# giraffe.net
KiCad netlist of a schematic drawn in EAGLE
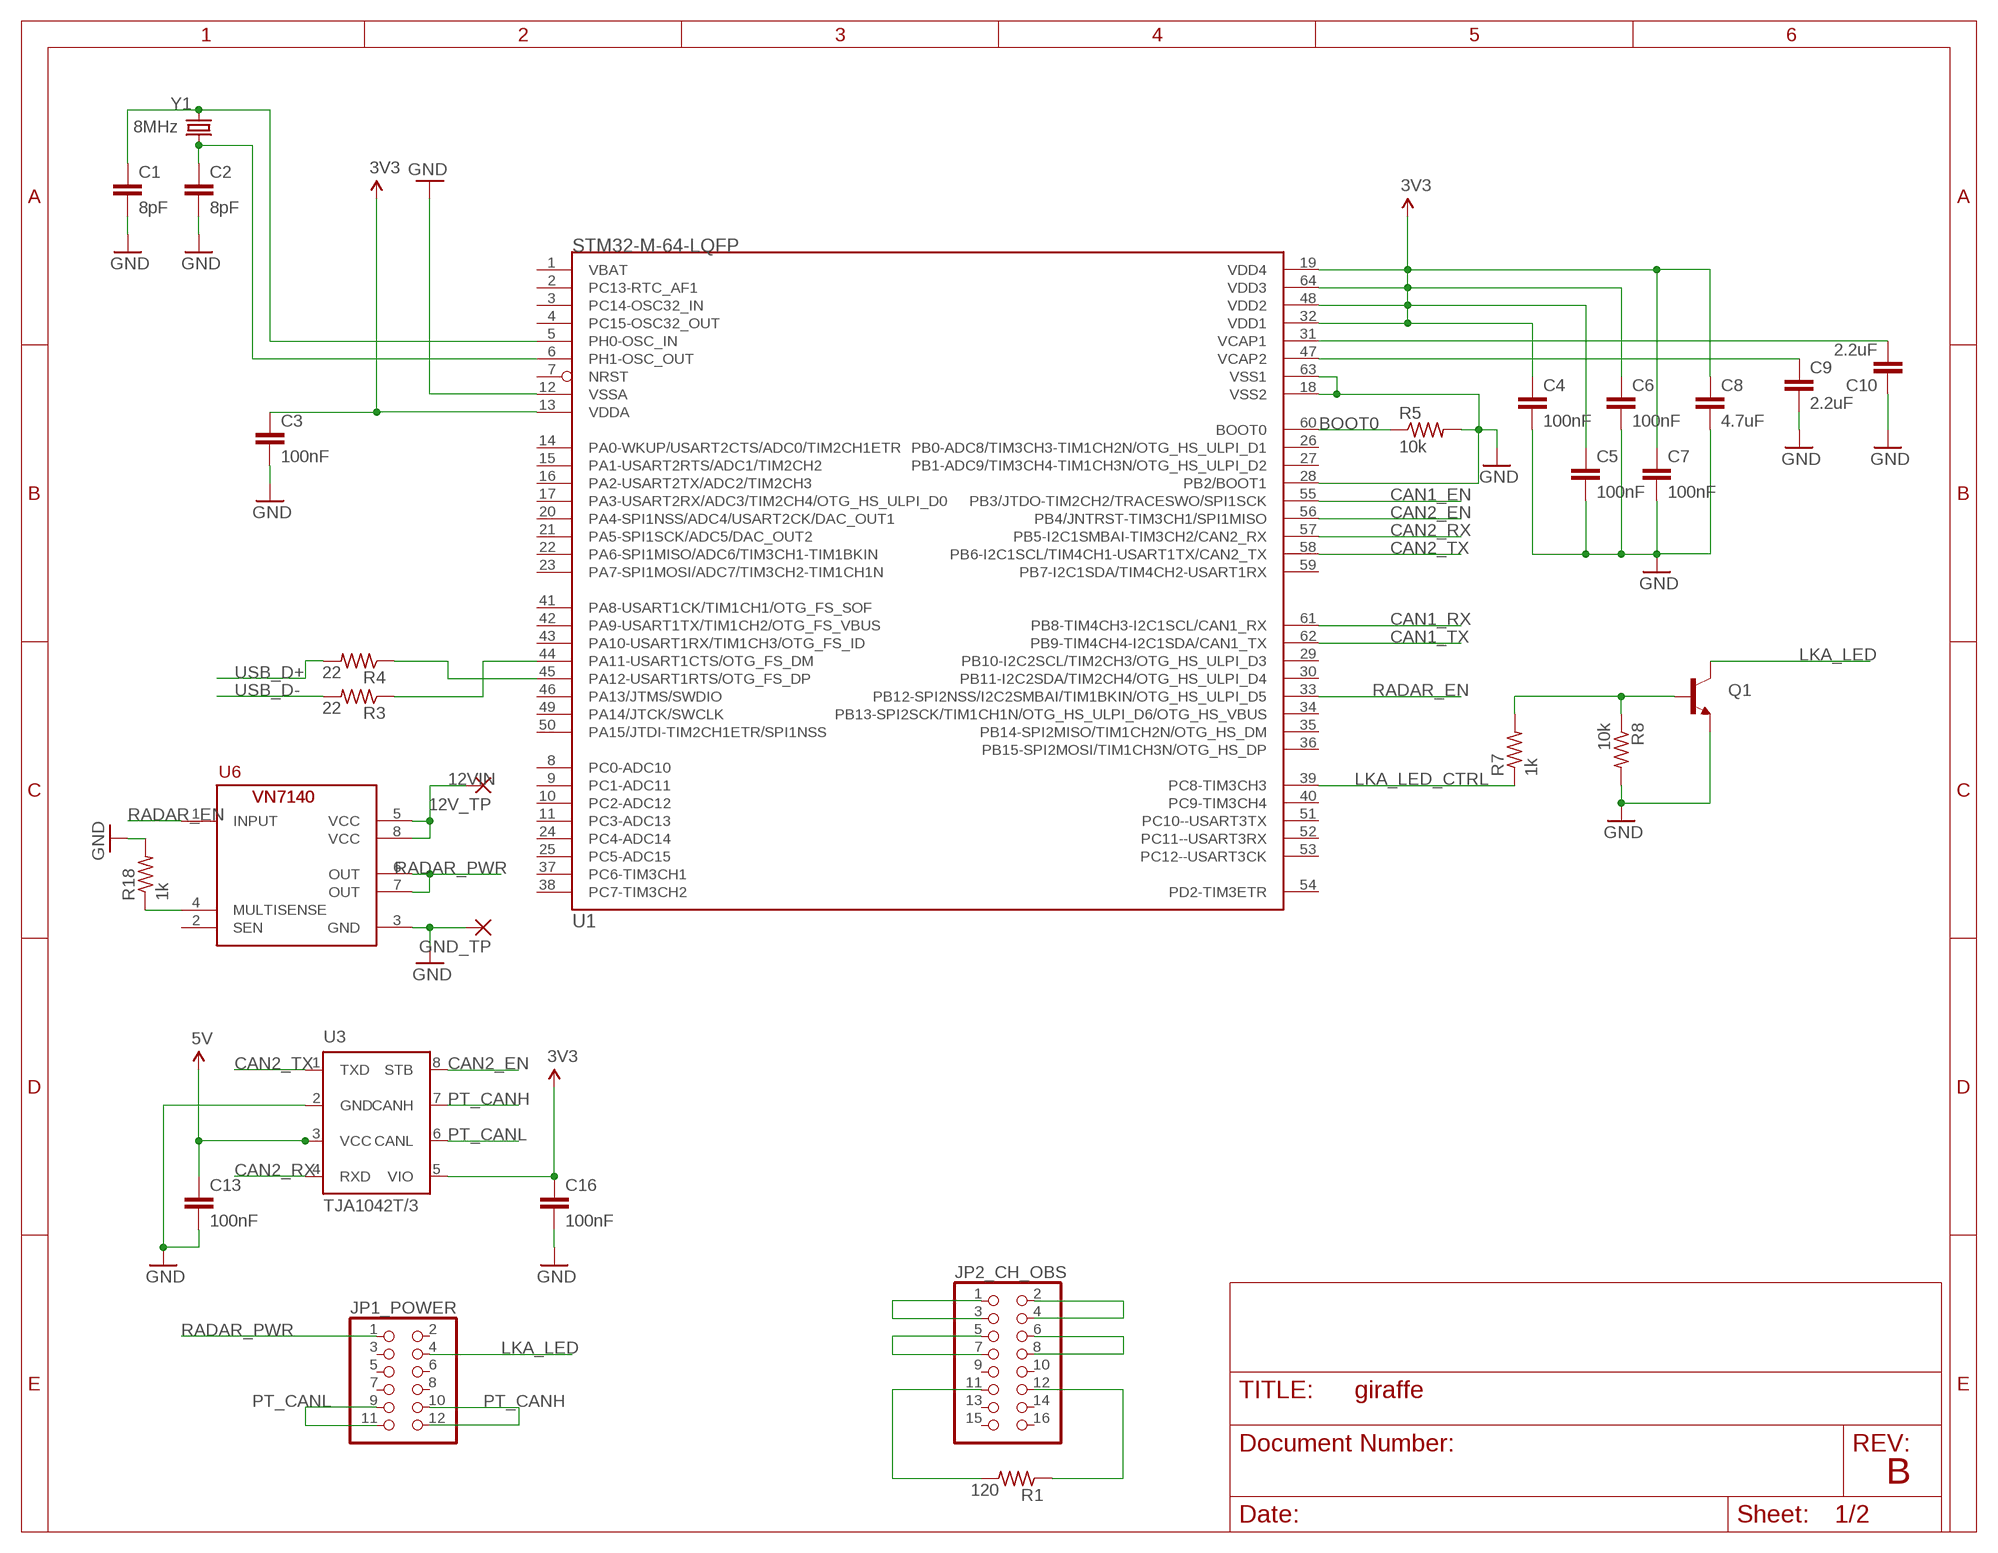
[diagram p0: schematic, sheet 1]
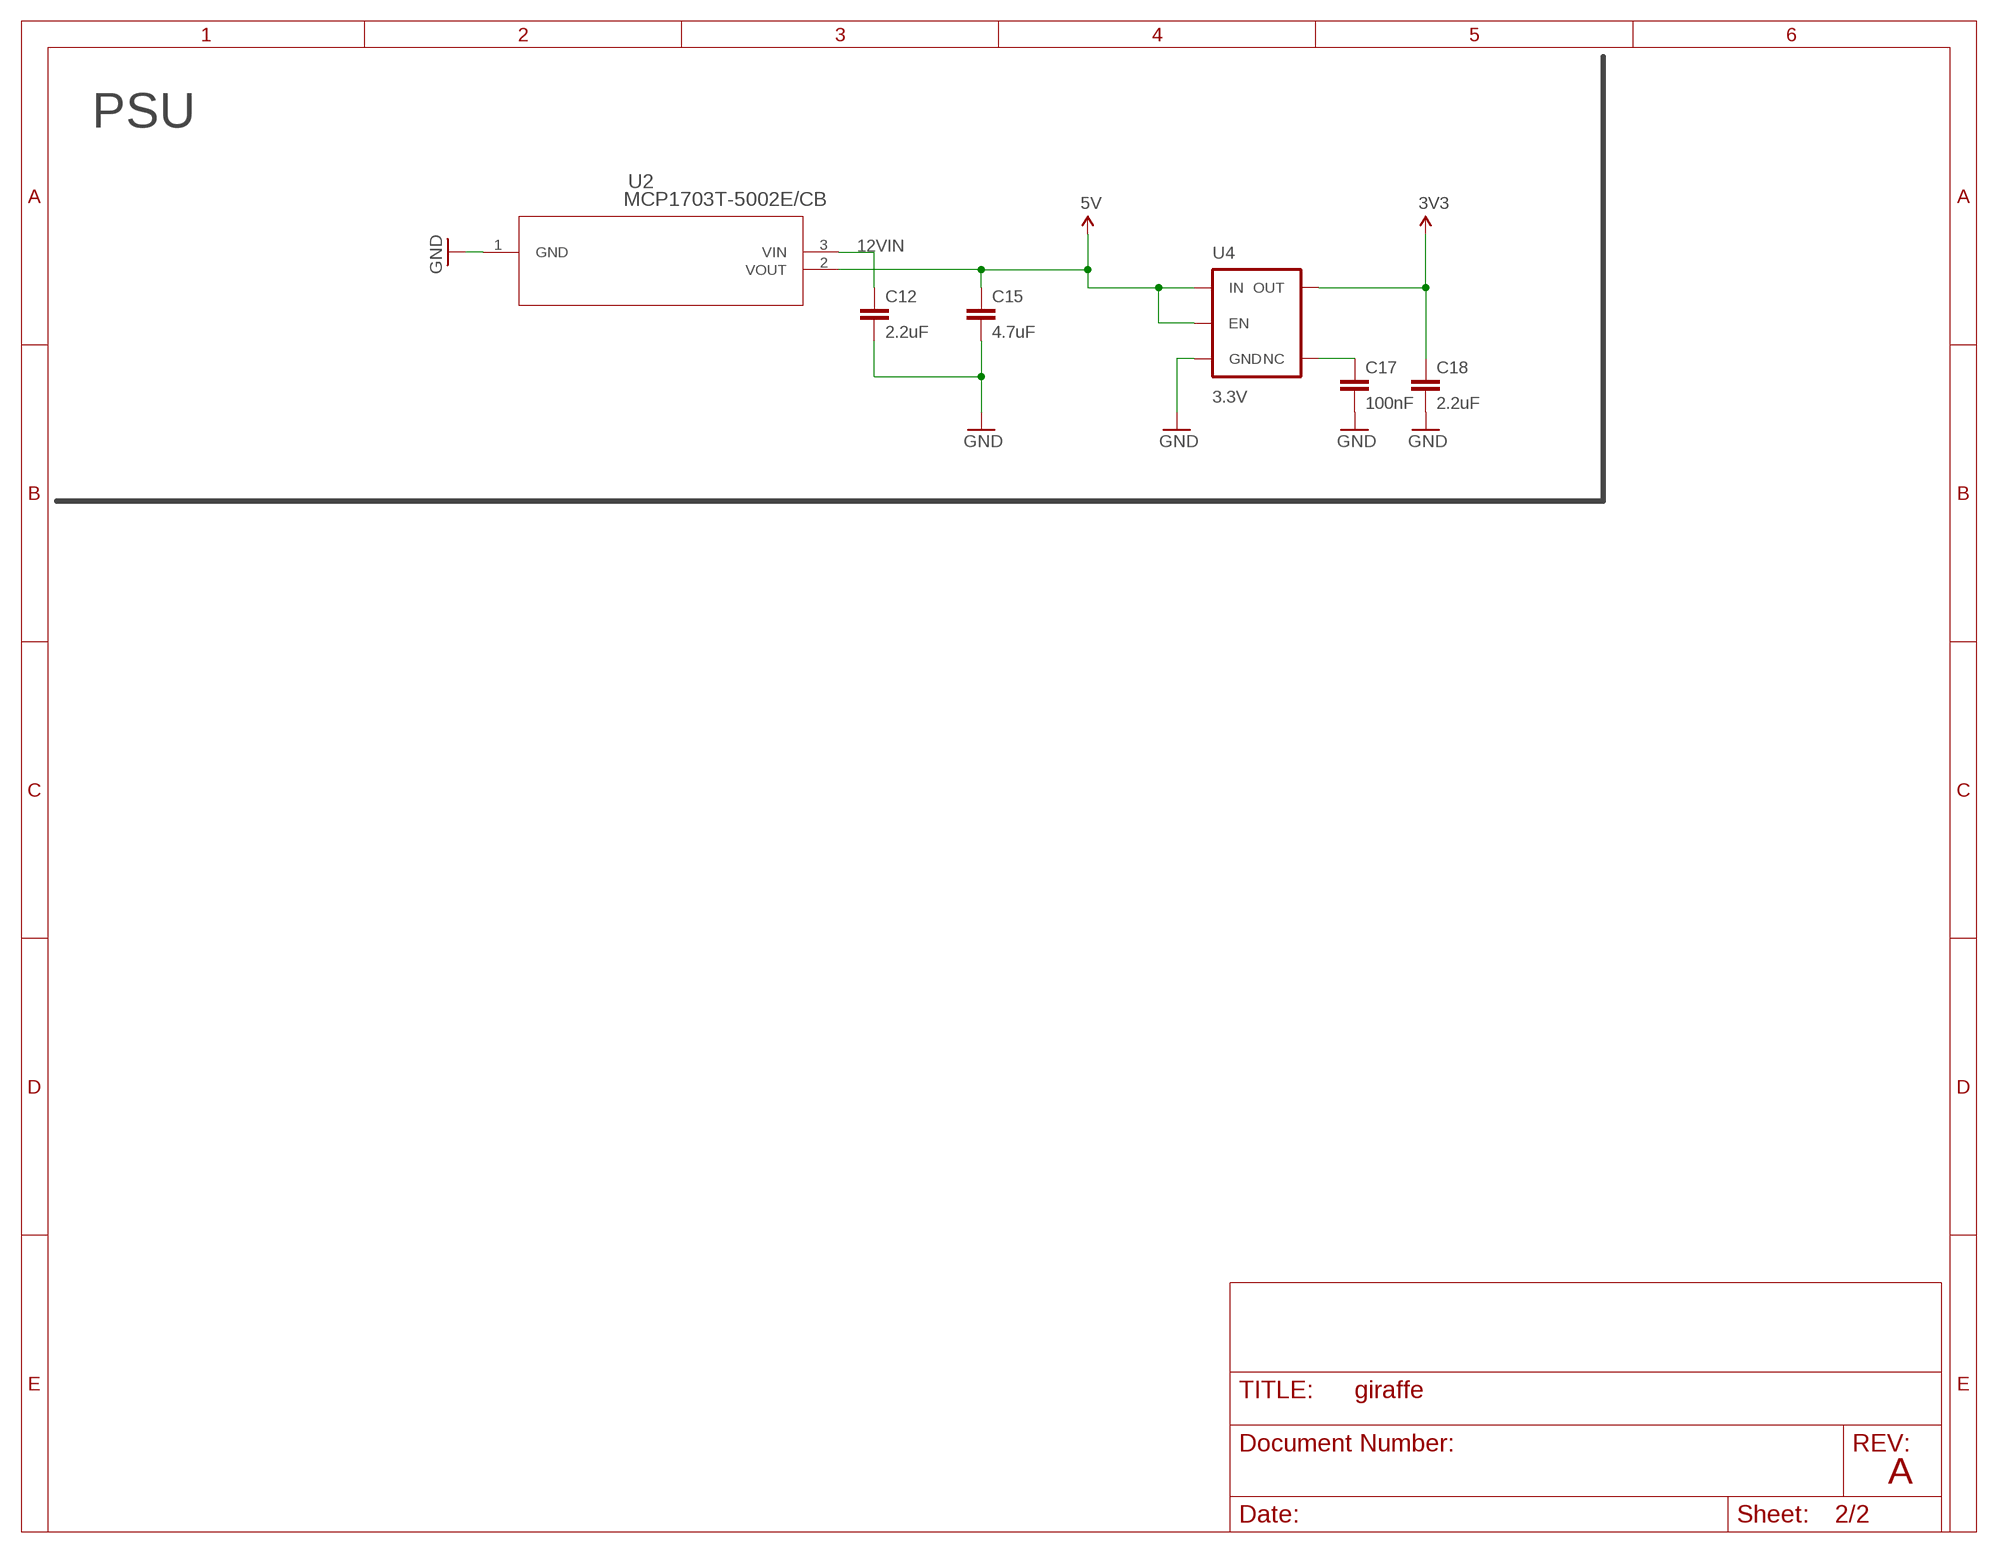
[diagram p1: schematic, sheet 2]

(export (version "E")
  (design (tool "Eeschema 10.0.6"))
  (components
    (comp (ref "C12")
      (value "2.2uF")
      (footprint "eagle-import:0805-CAP")
      (libsource (lib "eagle-import") (part "2.2UF-25V-+80/-20(0805)"))
    )
    (comp (ref "C15")
      (value "4.7uF")
      (footprint "eagle-import:0603-CAP")
      (libsource (lib "eagle-import") (part "CAP0603-CAP"))
    )
    (comp (ref "C17")
      (value "100nF")
      (footprint "eagle-import:0603-CAP")
      (libsource (lib "eagle-import") (part "CAP0603-CAP"))
    )
    (comp (ref "C18")
      (value "2.2uF")
      (footprint "eagle-import:0603-CAP")
      (libsource (lib "eagle-import") (part "CAP0603-CAP"))
    )
    (comp (ref "U2")
      (value "MCP1703T-5002E/CB")
      (footprint "eagle-import:SOT-23A_MC")
      (fields (field (name "MANUFACTURER_PART_NUMBER") "MCP1703T5002ECB"))
      (libsource (lib "eagle-import") (part "MCP1703T-5002E/CB"))
    )
    (comp (ref "U4")
      (value "3.3V")
      (footprint "eagle-import:SOT23-5")
      (libsource (lib "eagle-import") (part "V_REG_AP2112K-3.3V"))
    )
    (comp (ref "12V_TP")
      (value "2,15/1,0")
      (footprint "eagle-import:2,15_1,0")
      (libsource (lib "eagle-import") (part "2,15/1,0"))
    )
    (comp (ref "C1")
      (value "8pF")
      (footprint "eagle-import:0603-CAP")
      (libsource (lib "eagle-import") (part "1.0UF-16V-10%(0603)"))
    )
    (comp (ref "C2")
      (value "8pF")
      (footprint "eagle-import:0603-CAP")
      (libsource (lib "eagle-import") (part "1.0UF-16V-10%(0603)"))
    )
    (comp (ref "C3")
      (value "100nF")
      (footprint "eagle-import:0603-CAP")
      (libsource (lib "eagle-import") (part "1.0UF-16V-10%(0603)"))
    )
    (comp (ref "C4")
      (value "100nF")
      (footprint "eagle-import:0603-CAP")
      (libsource (lib "eagle-import") (part "1.0UF-16V-10%(0603)"))
    )
    (comp (ref "C5")
      (value "100nF")
      (footprint "eagle-import:0603-CAP")
      (libsource (lib "eagle-import") (part "1.0UF-16V-10%(0603)"))
    )
    (comp (ref "C6")
      (value "100nF")
      (footprint "eagle-import:0603-CAP")
      (libsource (lib "eagle-import") (part "0.1UF-25V-5%(0603)"))
    )
    (comp (ref "C7")
      (value "100nF")
      (footprint "eagle-import:0603-CAP")
      (libsource (lib "eagle-import") (part "1.0UF-16V-10%(0603)"))
    )
    (comp (ref "C8")
      (value "4.7uF")
      (footprint "eagle-import:0603-CAP")
      (libsource (lib "eagle-import") (part "1.0UF-16V-10%(0603)"))
    )
    (comp (ref "C9")
      (value "2.2uF")
      (footprint "eagle-import:0603-CAP")
      (libsource (lib "eagle-import") (part "1.0UF-16V-10%(0603)"))
    )
    (comp (ref "C10")
      (value "2.2uF")
      (footprint "eagle-import:0603-CAP")
      (libsource (lib "eagle-import") (part "1.0UF-16V-10%(0603)"))
    )
    (comp (ref "C13")
      (value "100nF")
      (footprint "eagle-import:0603-CAP")
      (libsource (lib "eagle-import") (part "CAP0603-CAP"))
    )
    (comp (ref "C16")
      (value "100nF")
      (footprint "eagle-import:0603-CAP")
      (libsource (lib "eagle-import") (part "CAP0603-CAP"))
    )
    (comp (ref "GND_TP")
      (value "2,15/1,0")
      (footprint "eagle-import:2,15_1,0")
      (libsource (lib "eagle-import") (part "2,15/1,0"))
    )
    (comp (ref "JP1_POWER")
      (value "PINHD-2X6")
      (footprint "eagle-import:2X06")
      (libsource (lib "eagle-import") (part "PINHD-2X6"))
    )
    (comp (ref "JP2_CH_OBS")
      (value "PINHD-2X8")
      (footprint "eagle-import:2X08")
      (libsource (lib "eagle-import") (part "PINHD-2X8"))
    )
    (comp (ref "Q1")
      (value "MMBT2222A")
      (footprint "eagle-import:SOT23-3")
      (libsource (lib "eagle-import") (part "TRANSISTOR_NPNMMBT2222A"))
    )
    (comp (ref "R1")
      (value "120")
      (footprint "eagle-import:R0603")
      (libsource (lib "eagle-import") (part "R-US_R0603"))
    )
    (comp (ref "R3")
      (value "22")
      (footprint "eagle-import:R0603")
      (libsource (lib "eagle-import") (part "R-US_R0603"))
    )
    (comp (ref "R4")
      (value "22")
      (footprint "eagle-import:R0603")
      (libsource (lib "eagle-import") (part "R-US_R0603"))
    )
    (comp (ref "R5")
      (value "10k")
      (footprint "eagle-import:R0603")
      (libsource (lib "eagle-import") (part "R-US_R0603"))
    )
    (comp (ref "R7")
      (value "1k")
      (footprint "eagle-import:R0603")
      (libsource (lib "eagle-import") (part "R-US_R0603"))
    )
    (comp (ref "R8")
      (value "10k")
      (footprint "eagle-import:R0603")
      (libsource (lib "eagle-import") (part "R-US_R0603"))
    )
    (comp (ref "R18")
      (value "1k")
      (footprint "eagle-import:R0603")
      (libsource (lib "eagle-import") (part "R-US_R0603"))
    )
    (comp (ref "U1")
      (value "STM32-M-64-LQFP")
      (footprint "eagle-import:LQFP64")
      (libsource (lib "eagle-import") (part "STM32-M-64-LQFP"))
    )
    (comp (ref "U3")
      (value "TJA1042T/3")
      (footprint "eagle-import:SO-8-L")
      (libsource (lib "eagle-import") (part "TJA1042T/3"))
    )
    (comp (ref "U6")
      (value "VN7140")
      (footprint "eagle-import:SO08")
      (libsource (lib "eagle-import") (part "VN7140"))
    )
    (comp (ref "Y1")
      (value "8MHz")
      (footprint "eagle-import:CRYSTAL-TXC-7A")
      (libsource (lib "eagle-import") (part "CRYSTALTXC-7A"))
    )
  )
  (nets
    (net (code "1") (name "3V3") (class "Default")
      (node (ref "C16") (pin "1") (pinfunction "1_1") (pintype "passive"))
      (node (ref "C18") (pin "1") (pinfunction "1_1") (pintype "passive"))
      (node (ref "C3") (pin "1") (pinfunction "1_1") (pintype "passive"))
      (node (ref "C4") (pin "1") (pinfunction "1_1") (pintype "passive"))
      (node (ref "C5") (pin "1") (pinfunction "1_1") (pintype "passive"))
      (node (ref "C6") (pin "1") (pinfunction "1_1") (pintype "passive"))
      (node (ref "C7") (pin "1") (pinfunction "1_1") (pintype "passive"))
      (node (ref "C8") (pin "1") (pinfunction "1_1") (pintype "passive"))
      (node (ref "U1") (pin "13") (pinfunction "VDDA_13") (pintype "power_in"))
      (node (ref "U1") (pin "19") (pinfunction "VDD4_19") (pintype "bidirectional"))
      (node (ref "U1") (pin "32") (pinfunction "VDD1_32") (pintype "power_in"))
      (node (ref "U1") (pin "48") (pinfunction "VDD2_48") (pintype "power_in"))
      (node (ref "U1") (pin "64") (pinfunction "VDD3_64") (pintype "power_in"))
      (node (ref "U3") (pin "5") (pinfunction "VIO_5") (pintype "power_in"))
      (node (ref "U4") (pin "5") (pinfunction "OUT_5") (pintype "passive"))
    )
    (net (code "2") (name "5V") (class "Default")
      (node (ref "C13") (pin "1") (pinfunction "1_1") (pintype "passive"))
      (node (ref "C15") (pin "1") (pinfunction "1_1") (pintype "passive"))
      (node (ref "U2") (pin "2") (pinfunction "VOUT_2") (pintype "passive"))
      (node (ref "U3") (pin "3") (pinfunction "VCC_3") (pintype "power_in"))
      (node (ref "U4") (pin "1") (pinfunction "IN_1") (pintype "input"))
      (node (ref "U4") (pin "3") (pinfunction "EN_3") (pintype "input"))
    )
    (net (code "3") (name "12VIN") (class "Default")
      (node (ref "12V_TP") (pin "1") (pinfunction "P_1") (pintype "passive"))
      (node (ref "C12") (pin "1") (pinfunction "1_1") (pintype "passive"))
      (node (ref "U2") (pin "3") (pinfunction "VIN_3") (pintype "passive"))
      (node (ref "U6") (pin "5") (pinfunction "VCC_5") (pintype "bidirectional"))
      (node (ref "U6") (pin "8") (pinfunction "VCC_8") (pintype "bidirectional"))
    )
    (net (code "4") (name "BOOT0") (class "Default")
      (node (ref "R5") (pin "1") (pinfunction "1_1") (pintype "passive"))
      (node (ref "U1") (pin "60") (pinfunction "BOOT0_60") (pintype "input"))
    )
    (net (code "5") (name "CAN1_EN") (class "Default")
      (node (ref "U1") (pin "55") (pinfunction "PB3/JTDO-TIM2CH2/TRACESWO/SPI1SCK_55") (pintype "bidirectional"))
    )
    (net (code "6") (name "CAN1_RX") (class "Default")
      (node (ref "U1") (pin "61") (pinfunction "PB8-TIM4CH3-I2C1SCL/CAN1_RX_61") (pintype "bidirectional"))
    )
    (net (code "7") (name "CAN1_TX") (class "Default")
      (node (ref "U1") (pin "62") (pinfunction "PB9-TIM4CH4-I2C1SDA/CAN1_TX_62") (pintype "bidirectional"))
    )
    (net (code "8") (name "CAN2_EN") (class "Default")
      (node (ref "U1") (pin "56") (pinfunction "PB4/JNTRST-TIM3CH1/SPI1MISO_56") (pintype "bidirectional"))
      (node (ref "U3") (pin "8") (pinfunction "STB_8") (pintype "input"))
    )
    (net (code "9") (name "CAN2_RX") (class "Default")
      (node (ref "U1") (pin "57") (pinfunction "PB5-I2C1SMBAI-TIM3CH2/CAN2_RX_57") (pintype "bidirectional"))
      (node (ref "U3") (pin "4") (pinfunction "RXD_4") (pintype "output"))
    )
    (net (code "10") (name "CAN2_TX") (class "Default")
      (node (ref "U1") (pin "58") (pinfunction "PB6-I2C1SCL/TIM4CH1-USART1TX/CAN2_TX_58") (pintype "bidirectional"))
      (node (ref "U3") (pin "1") (pinfunction "TXD_1") (pintype "input"))
    )
    (net (code "11") (name "GND") (class "Default")
      (node (ref "C1") (pin "2") (pinfunction "2_2") (pintype "passive"))
      (node (ref "C10") (pin "1") (pinfunction "1_1") (pintype "passive"))
      (node (ref "C12") (pin "2") (pinfunction "2_2") (pintype "passive"))
      (node (ref "C13") (pin "2") (pinfunction "2_2") (pintype "passive"))
      (node (ref "C15") (pin "2") (pinfunction "2_2") (pintype "passive"))
      (node (ref "C16") (pin "2") (pinfunction "2_2") (pintype "passive"))
      (node (ref "C17") (pin "2") (pinfunction "2_2") (pintype "passive"))
      (node (ref "C18") (pin "2") (pinfunction "2_2") (pintype "passive"))
      (node (ref "C2") (pin "2") (pinfunction "2_2") (pintype "passive"))
      (node (ref "C3") (pin "2") (pinfunction "2_2") (pintype "passive"))
      (node (ref "C4") (pin "2") (pinfunction "2_2") (pintype "passive"))
      (node (ref "C5") (pin "2") (pinfunction "2_2") (pintype "passive"))
      (node (ref "C6") (pin "2") (pinfunction "2_2") (pintype "passive"))
      (node (ref "C7") (pin "2") (pinfunction "2_2") (pintype "passive"))
      (node (ref "C8") (pin "2") (pinfunction "2_2") (pintype "passive"))
      (node (ref "C9") (pin "2") (pinfunction "2_2") (pintype "passive"))
      (node (ref "GND_TP") (pin "1") (pinfunction "P_1") (pintype "passive"))
      (node (ref "Q1") (pin "2") (pinfunction "E_2") (pintype "passive"))
      (node (ref "R18") (pin "2") (pinfunction "2_2") (pintype "passive"))
      (node (ref "R5") (pin "2") (pinfunction "2_2") (pintype "passive"))
      (node (ref "R8") (pin "2") (pinfunction "2_2") (pintype "passive"))
      (node (ref "U1") (pin "12") (pinfunction "VSSA_12") (pintype "power_in"))
      (node (ref "U1") (pin "18") (pinfunction "VSS2_18") (pintype "bidirectional"))
      (node (ref "U1") (pin "28") (pinfunction "PB2/BOOT1_28") (pintype "bidirectional"))
      (node (ref "U1") (pin "63") (pinfunction "VSS1_63") (pintype "power_in"))
      (node (ref "U2") (pin "1") (pinfunction "GND_1") (pintype "passive"))
      (node (ref "U3") (pin "2") (pinfunction "GND_2") (pintype "passive"))
      (node (ref "U4") (pin "2") (pinfunction "GND_2") (pintype "input"))
      (node (ref "U6") (pin "3") (pinfunction "GND_3") (pintype "bidirectional"))
    )
    (net (code "12") (name "LKA_LED") (class "Default")
      (node (ref "JP1_POWER") (pin "4") (pinfunction "4_4") (pintype "passive"))
      (node (ref "Q1") (pin "3") (pinfunction "C_3") (pintype "passive"))
    )
    (net (code "13") (name "LKA_LED_CTRL") (class "Default")
      (node (ref "R7") (pin "1") (pinfunction "1_1") (pintype "passive"))
      (node (ref "U1") (pin "39") (pinfunction "PC8-TIM3CH3_39") (pintype "bidirectional"))
    )
    (net (code "14") (name "Net-(JP2_CH_OBS-Pad1)") (class "Default")
      (node (ref "JP2_CH_OBS") (pin "1") (pinfunction "1_1") (pintype "passive"))
      (node (ref "JP2_CH_OBS") (pin "3") (pinfunction "3_3") (pintype "passive"))
    )
    (net (code "15") (name "Net-(JP2_CH_OBS-Pad2)") (class "Default")
      (node (ref "JP2_CH_OBS") (pin "2") (pinfunction "2_2") (pintype "passive"))
      (node (ref "JP2_CH_OBS") (pin "4") (pinfunction "4_4") (pintype "passive"))
    )
    (net (code "16") (name "Net-(JP2_CH_OBS-Pad5)") (class "Default")
      (node (ref "JP2_CH_OBS") (pin "5") (pinfunction "5_5") (pintype "passive"))
      (node (ref "JP2_CH_OBS") (pin "7") (pinfunction "7_7") (pintype "passive"))
    )
    (net (code "17") (name "Net-(JP2_CH_OBS-Pad6)") (class "Default")
      (node (ref "JP2_CH_OBS") (pin "6") (pinfunction "6_6") (pintype "passive"))
      (node (ref "JP2_CH_OBS") (pin "8") (pinfunction "8_8") (pintype "passive"))
    )
    (net (code "18") (name "Net-(JP2_CH_OBS-Pad11)") (class "Default")
      (node (ref "JP2_CH_OBS") (pin "11") (pinfunction "11_11") (pintype "passive"))
      (node (ref "R1") (pin "2") (pinfunction "2_2") (pintype "passive"))
    )
    (net (code "19") (name "Net-(JP2_CH_OBS-Pad12)") (class "Default")
      (node (ref "JP2_CH_OBS") (pin "12") (pinfunction "12_12") (pintype "passive"))
      (node (ref "R1") (pin "1") (pinfunction "1_1") (pintype "passive"))
    )
    (net (code "20") (name "Net-(Q1-B)") (class "Default")
      (node (ref "Q1") (pin "1") (pinfunction "B_1") (pintype "passive"))
      (node (ref "R7") (pin "2") (pinfunction "2_2") (pintype "passive"))
      (node (ref "R8") (pin "1") (pinfunction "1_1") (pintype "passive"))
    )
    (net (code "21") (name "Net-(U1-PA11-USART1CTS{slash}OTG_FS_DM)") (class "Default")
      (node (ref "R3") (pin "1") (pinfunction "1_1") (pintype "passive"))
      (node (ref "U1") (pin "44") (pinfunction "PA11-USART1CTS/OTG_FS_DM_44") (pintype "bidirectional"))
    )
    (net (code "22") (name "Net-(U1-PA12-USART1RTS{slash}OTG_FS_DP)") (class "Default")
      (node (ref "R4") (pin "1") (pinfunction "1_1") (pintype "passive"))
      (node (ref "U1") (pin "45") (pinfunction "PA12-USART1RTS/OTG_FS_DP_45") (pintype "bidirectional"))
    )
    (net (code "23") (name "Net-(U1-PH0-OSC_IN)") (class "Default")
      (node (ref "C1") (pin "1") (pinfunction "1_1") (pintype "passive"))
      (node (ref "U1") (pin "5") (pinfunction "PH0-OSC_IN_5") (pintype "input"))
      (node (ref "Y1") (pin "P$1") (pinfunction "1_P$1") (pintype "passive"))
    )
    (net (code "24") (name "Net-(U1-PH1-OSC_OUT)") (class "Default")
      (node (ref "C2") (pin "1") (pinfunction "1_1") (pintype "passive"))
      (node (ref "U1") (pin "6") (pinfunction "PH1-OSC_OUT_6") (pintype "output"))
      (node (ref "Y1") (pin "P$2") (pinfunction "2_P$2") (pintype "passive"))
    )
    (net (code "25") (name "Net-(U1-VCAP1)") (class "Default")
      (node (ref "C10") (pin "2") (pinfunction "2_2") (pintype "passive"))
      (node (ref "U1") (pin "31") (pinfunction "VCAP1_31") (pintype "power_in"))
    )
    (net (code "26") (name "Net-(U1-VCAP2)") (class "Default")
      (node (ref "C9") (pin "1") (pinfunction "1_1") (pintype "passive"))
      (node (ref "U1") (pin "47") (pinfunction "VCAP2_47") (pintype "power_in"))
    )
    (net (code "27") (name "Net-(U4-NC)") (class "Default")
      (node (ref "C17") (pin "1") (pinfunction "1_1") (pintype "passive"))
      (node (ref "U4") (pin "4") (pinfunction "NC_4") (pintype "input"))
    )
    (net (code "28") (name "Net-(U6-MULTISENSE)") (class "Default")
      (node (ref "R18") (pin "1") (pinfunction "1_1") (pintype "passive"))
      (node (ref "U6") (pin "4") (pinfunction "MULTISENSE_4") (pintype "bidirectional"))
    )
    (net (code "29") (name "PT_CANH") (class "Default")
      (node (ref "JP1_POWER") (pin "10") (pinfunction "10_10") (pintype "passive"))
      (node (ref "JP1_POWER") (pin "12") (pinfunction "12_12") (pintype "passive"))
      (node (ref "U3") (pin "7") (pinfunction "CANH_7") (pintype "output"))
    )
    (net (code "30") (name "PT_CANL") (class "Default")
      (node (ref "JP1_POWER") (pin "11") (pinfunction "11_11") (pintype "passive"))
      (node (ref "JP1_POWER") (pin "9") (pinfunction "9_9") (pintype "passive"))
      (node (ref "U3") (pin "6") (pinfunction "CANL_6") (pintype "output"))
    )
    (net (code "31") (name "RADAR_EN") (class "Default")
      (node (ref "U1") (pin "33") (pinfunction "PB12-SPI2NSS/I2C2SMBAI/TIM1BKIN/OTG_HS_ULPI_D5_33") (pintype "bidirectional"))
      (node (ref "U6") (pin "1") (pinfunction "INPUT_1") (pintype "bidirectional"))
    )
    (net (code "32") (name "RADAR_PWR") (class "Default")
      (node (ref "JP1_POWER") (pin "1") (pinfunction "1_1") (pintype "passive"))
      (node (ref "U6") (pin "6") (pinfunction "OUT_6") (pintype "bidirectional"))
      (node (ref "U6") (pin "7") (pinfunction "OUT_7") (pintype "bidirectional"))
    )
    (net (code "33") (name "USB_D+") (class "Default")
      (node (ref "R4") (pin "2") (pinfunction "2_2") (pintype "passive"))
    )
    (net (code "34") (name "USB_D-") (class "Default")
      (node (ref "R3") (pin "2") (pinfunction "2_2") (pintype "passive"))
    )
    (net (code "35") (name "VBAT") (class "Default")
      (node (ref "U1") (pin "1") (pinfunction "VBAT_1") (pintype "power_in"))
    )
    (net (code "36") (name "unconnected-(JP1_POWER-Pad2)") (class "Default")
      (node (ref "JP1_POWER") (pin "2") (pinfunction "2_2") (pintype "passive"))
    )
    (net (code "37") (name "unconnected-(JP1_POWER-Pad3)") (class "Default")
      (node (ref "JP1_POWER") (pin "3") (pinfunction "3_3") (pintype "passive"))
    )
    (net (code "38") (name "unconnected-(JP1_POWER-Pad5)") (class "Default")
      (node (ref "JP1_POWER") (pin "5") (pinfunction "5_5") (pintype "passive"))
    )
    (net (code "39") (name "unconnected-(JP1_POWER-Pad6)") (class "Default")
      (node (ref "JP1_POWER") (pin "6") (pinfunction "6_6") (pintype "passive"))
    )
    (net (code "40") (name "unconnected-(JP1_POWER-Pad7)") (class "Default")
      (node (ref "JP1_POWER") (pin "7") (pinfunction "7_7") (pintype "passive"))
    )
    (net (code "41") (name "unconnected-(JP1_POWER-Pad8)") (class "Default")
      (node (ref "JP1_POWER") (pin "8") (pinfunction "8_8") (pintype "passive"))
    )
    (net (code "42") (name "unconnected-(JP2_CH_OBS-Pad9)") (class "Default")
      (node (ref "JP2_CH_OBS") (pin "9") (pinfunction "9_9") (pintype "passive"))
    )
    (net (code "43") (name "unconnected-(JP2_CH_OBS-Pad10)") (class "Default")
      (node (ref "JP2_CH_OBS") (pin "10") (pinfunction "10_10") (pintype "passive"))
    )
    (net (code "44") (name "unconnected-(JP2_CH_OBS-Pad13)") (class "Default")
      (node (ref "JP2_CH_OBS") (pin "13") (pinfunction "13_13") (pintype "passive"))
    )
    (net (code "45") (name "unconnected-(JP2_CH_OBS-Pad14)") (class "Default")
      (node (ref "JP2_CH_OBS") (pin "14") (pinfunction "14_14") (pintype "passive"))
    )
    (net (code "46") (name "unconnected-(JP2_CH_OBS-Pad15)") (class "Default")
      (node (ref "JP2_CH_OBS") (pin "15") (pinfunction "15_15") (pintype "passive"))
    )
    (net (code "47") (name "unconnected-(JP2_CH_OBS-Pad16)") (class "Default")
      (node (ref "JP2_CH_OBS") (pin "16") (pinfunction "16_16") (pintype "passive"))
    )
    (net (code "48") (name "unconnected-(U1-NRST-Pad7)") (class "Default")
      (node (ref "U1") (pin "7") (pinfunction "NRST_7") (pintype "bidirectional"))
    )
    (net (code "49") (name "unconnected-(U1-PA0-WKUP{slash}USART2CTS{slash}ADC0{slash}TIM2CH1ETR-Pad14)") (class "Default")
      (node (ref "U1") (pin "14") (pinfunction "PA0-WKUP/USART2CTS/ADC0/TIM2CH1ETR_14") (pintype "bidirectional"))
    )
    (net (code "50") (name "unconnected-(U1-PA1-USART2RTS{slash}ADC1{slash}TIM2CH2-Pad15)") (class "Default")
      (node (ref "U1") (pin "15") (pinfunction "PA1-USART2RTS/ADC1/TIM2CH2_15") (pintype "bidirectional"))
    )
    (net (code "51") (name "unconnected-(U1-PA2-USART2TX{slash}ADC2{slash}TIM2CH3-Pad16)") (class "Default")
      (node (ref "U1") (pin "16") (pinfunction "PA2-USART2TX/ADC2/TIM2CH3_16") (pintype "bidirectional"))
    )
    (net (code "52") (name "unconnected-(U1-PA3-USART2RX{slash}ADC3{slash}TIM2CH4{slash}OTG_HS_ULPI_D0-Pad17)") (class "Default")
      (node (ref "U1") (pin "17") (pinfunction "PA3-USART2RX/ADC3/TIM2CH4/OTG_HS_ULPI_D0_17") (pintype "bidirectional"))
    )
    (net (code "53") (name "unconnected-(U1-PA4-SPI1NSS{slash}ADC4{slash}USART2CK{slash}DAC_OUT1-Pad20)") (class "Default")
      (node (ref "U1") (pin "20") (pinfunction "PA4-SPI1NSS/ADC4/USART2CK/DAC_OUT1_20") (pintype "bidirectional"))
    )
    (net (code "54") (name "unconnected-(U1-PA5-SPI1SCK{slash}ADC5{slash}DAC_OUT2-Pad21)") (class "Default")
      (node (ref "U1") (pin "21") (pinfunction "PA5-SPI1SCK/ADC5/DAC_OUT2_21") (pintype "bidirectional"))
    )
    (net (code "55") (name "unconnected-(U1-PA6-SPI1MISO{slash}ADC6{slash}TIM3CH1-TIM1BKIN-Pad22)") (class "Default")
      (node (ref "U1") (pin "22") (pinfunction "PA6-SPI1MISO/ADC6/TIM3CH1-TIM1BKIN_22") (pintype "bidirectional"))
    )
    (net (code "56") (name "unconnected-(U1-PA7-SPI1MOSI{slash}ADC7{slash}TIM3CH2-TIM1CH1N-Pad23)") (class "Default")
      (node (ref "U1") (pin "23") (pinfunction "PA7-SPI1MOSI/ADC7/TIM3CH2-TIM1CH1N_23") (pintype "bidirectional"))
    )
    (net (code "57") (name "unconnected-(U1-PA8-USART1CK{slash}TIM1CH1{slash}OTG_FS_SOF-Pad41)") (class "Default")
      (node (ref "U1") (pin "41") (pinfunction "PA8-USART1CK/TIM1CH1/OTG_FS_SOF_41") (pintype "bidirectional"))
    )
    (net (code "58") (name "unconnected-(U1-PA9-USART1TX{slash}TIM1CH2{slash}OTG_FS_VBUS-Pad42)") (class "Default")
      (node (ref "U1") (pin "42") (pinfunction "PA9-USART1TX/TIM1CH2/OTG_FS_VBUS_42") (pintype "bidirectional"))
    )
    (net (code "59") (name "unconnected-(U1-PA10-USART1RX{slash}TIM1CH3{slash}OTG_FS_ID-Pad43)") (class "Default")
      (node (ref "U1") (pin "43") (pinfunction "PA10-USART1RX/TIM1CH3/OTG_FS_ID_43") (pintype "bidirectional"))
    )
    (net (code "60") (name "unconnected-(U1-PA13{slash}JTMS{slash}SWDIO-Pad46)") (class "Default")
      (node (ref "U1") (pin "46") (pinfunction "PA13/JTMS/SWDIO_46") (pintype "bidirectional"))
    )
    (net (code "61") (name "unconnected-(U1-PA14{slash}JTCK{slash}SWCLK-Pad49)") (class "Default")
      (node (ref "U1") (pin "49") (pinfunction "PA14/JTCK/SWCLK_49") (pintype "bidirectional"))
    )
    (net (code "62") (name "unconnected-(U1-PA15{slash}JTDI-TIM2CH1ETR{slash}SPI1NSS-Pad50)") (class "Default")
      (node (ref "U1") (pin "50") (pinfunction "PA15/JTDI-TIM2CH1ETR/SPI1NSS_50") (pintype "bidirectional"))
    )
    (net (code "63") (name "unconnected-(U1-PB0-ADC8{slash}TIM3CH3-TIM1CH2N{slash}OTG_HS_ULPI_D1-Pad26)") (class "Default")
      (node (ref "U1") (pin "26") (pinfunction "PB0-ADC8/TIM3CH3-TIM1CH2N/OTG_HS_ULPI_D1_26") (pintype "bidirectional"))
    )
    (net (code "64") (name "unconnected-(U1-PB1-ADC9{slash}TIM3CH4-TIM1CH3N{slash}OTG_HS_ULPI_D2-Pad27)") (class "Default")
      (node (ref "U1") (pin "27") (pinfunction "PB1-ADC9/TIM3CH4-TIM1CH3N/OTG_HS_ULPI_D2_27") (pintype "bidirectional"))
    )
    (net (code "65") (name "unconnected-(U1-PB7-I2C1SDA{slash}TIM4CH2-USART1RX-Pad59)") (class "Default")
      (node (ref "U1") (pin "59") (pinfunction "PB7-I2C1SDA/TIM4CH2-USART1RX_59") (pintype "bidirectional"))
    )
    (net (code "66") (name "unconnected-(U1-PB10-I2C2SCL{slash}TIM2CH3{slash}OTG_HS_ULPI_D3-Pad29)") (class "Default")
      (node (ref "U1") (pin "29") (pinfunction "PB10-I2C2SCL/TIM2CH3/OTG_HS_ULPI_D3_29") (pintype "bidirectional"))
    )
    (net (code "67") (name "unconnected-(U1-PB11-I2C2SDA{slash}TIM2CH4{slash}OTG_HS_ULPI_D4-Pad30)") (class "Default")
      (node (ref "U1") (pin "30") (pinfunction "PB11-I2C2SDA/TIM2CH4/OTG_HS_ULPI_D4_30") (pintype "bidirectional"))
    )
    (net (code "68") (name "unconnected-(U1-PB13-SPI2SCK{slash}TIM1CH1N{slash}OTG_HS_ULPI_D6{slash}OTG_HS_VBUS-Pad34)") (class "Default")
      (node (ref "U1") (pin "34") (pinfunction "PB13-SPI2SCK/TIM1CH1N/OTG_HS_ULPI_D6/OTG_HS_VBUS_34") (pintype "bidirectional"))
    )
    (net (code "69") (name "unconnected-(U1-PB14-SPI2MISO{slash}TIM1CH2N{slash}OTG_HS_DM-Pad35)") (class "Default")
      (node (ref "U1") (pin "35") (pinfunction "PB14-SPI2MISO/TIM1CH2N/OTG_HS_DM_35") (pintype "bidirectional"))
    )
    (net (code "70") (name "unconnected-(U1-PB15-SPI2MOSI{slash}TIM1CH3N{slash}OTG_HS_DP-Pad36)") (class "Default")
      (node (ref "U1") (pin "36") (pinfunction "PB15-SPI2MOSI/TIM1CH3N/OTG_HS_DP_36") (pintype "bidirectional"))
    )
    (net (code "71") (name "unconnected-(U1-PC0-ADC10-Pad8)") (class "Default")
      (node (ref "U1") (pin "8") (pinfunction "PC0-ADC10_8") (pintype "bidirectional"))
    )
    (net (code "72") (name "unconnected-(U1-PC1-ADC11-Pad9)") (class "Default")
      (node (ref "U1") (pin "9") (pinfunction "PC1-ADC11_9") (pintype "bidirectional"))
    )
    (net (code "73") (name "unconnected-(U1-PC2-ADC12-Pad10)") (class "Default")
      (node (ref "U1") (pin "10") (pinfunction "PC2-ADC12_10") (pintype "bidirectional"))
    )
    (net (code "74") (name "unconnected-(U1-PC3-ADC13-Pad11)") (class "Default")
      (node (ref "U1") (pin "11") (pinfunction "PC3-ADC13_11") (pintype "bidirectional"))
    )
    (net (code "75") (name "unconnected-(U1-PC4-ADC14-Pad24)") (class "Default")
      (node (ref "U1") (pin "24") (pinfunction "PC4-ADC14_24") (pintype "bidirectional"))
    )
    (net (code "76") (name "unconnected-(U1-PC5-ADC15-Pad25)") (class "Default")
      (node (ref "U1") (pin "25") (pinfunction "PC5-ADC15_25") (pintype "bidirectional"))
    )
    (net (code "77") (name "unconnected-(U1-PC6-TIM3CH1-Pad37)") (class "Default")
      (node (ref "U1") (pin "37") (pinfunction "PC6-TIM3CH1_37") (pintype "bidirectional"))
    )
    (net (code "78") (name "unconnected-(U1-PC7-TIM3CH2-Pad38)") (class "Default")
      (node (ref "U1") (pin "38") (pinfunction "PC7-TIM3CH2_38") (pintype "bidirectional"))
    )
    (net (code "79") (name "unconnected-(U1-PC9-TIM3CH4-Pad40)") (class "Default")
      (node (ref "U1") (pin "40") (pinfunction "PC9-TIM3CH4_40") (pintype "bidirectional"))
    )
    (net (code "80") (name "unconnected-(U1-PC10--USART3TX-Pad51)") (class "Default")
      (node (ref "U1") (pin "51") (pinfunction "PC10--USART3TX_51") (pintype "bidirectional"))
    )
    (net (code "81") (name "unconnected-(U1-PC11--USART3RX-Pad52)") (class "Default")
      (node (ref "U1") (pin "52") (pinfunction "PC11--USART3RX_52") (pintype "bidirectional"))
    )
    (net (code "82") (name "unconnected-(U1-PC12--USART3CK-Pad53)") (class "Default")
      (node (ref "U1") (pin "53") (pinfunction "PC12--USART3CK_53") (pintype "bidirectional"))
    )
    (net (code "83") (name "unconnected-(U1-PC13-RTC_AF1-Pad2)") (class "Default")
      (node (ref "U1") (pin "2") (pinfunction "PC13-RTC_AF1_2") (pintype "bidirectional"))
    )
    (net (code "84") (name "unconnected-(U1-PC14-OSC32_IN-Pad3)") (class "Default")
      (node (ref "U1") (pin "3") (pinfunction "PC14-OSC32_IN_3") (pintype "bidirectional"))
    )
    (net (code "85") (name "unconnected-(U1-PC15-OSC32_OUT-Pad4)") (class "Default")
      (node (ref "U1") (pin "4") (pinfunction "PC15-OSC32_OUT_4") (pintype "bidirectional"))
    )
    (net (code "86") (name "unconnected-(U1-PD2-TIM3ETR-Pad54)") (class "Default")
      (node (ref "U1") (pin "54") (pinfunction "PD2-TIM3ETR_54") (pintype "bidirectional"))
    )
    (net (code "87") (name "unconnected-(U6-SEN-Pad2)") (class "Default")
      (node (ref "U6") (pin "2") (pinfunction "SEN_2") (pintype "bidirectional"))
    )
  )
)
